# Mach_cau_H_-_Phuc.net
KiCad netlist of a schematic drawn in Altium Designer
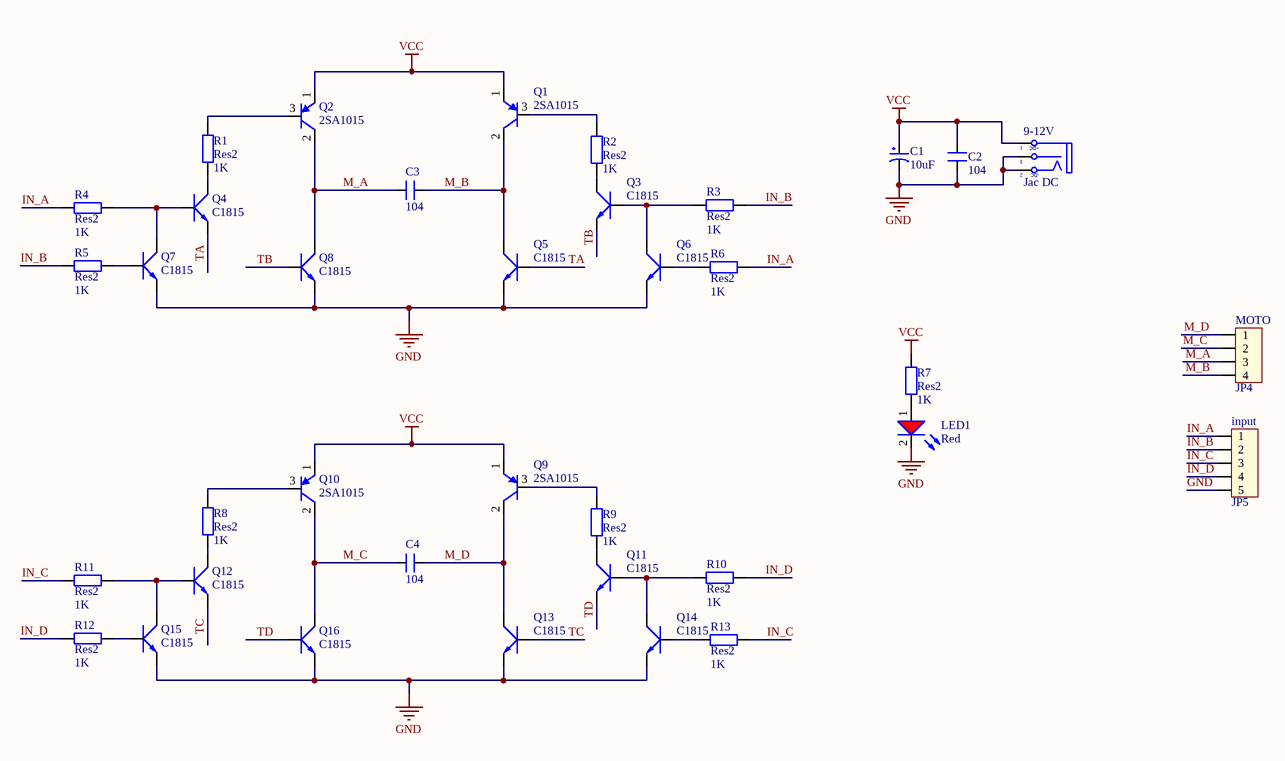
[diagram p0: Mach cau H - Phuc.SchDoc]

(export (version "E")
  (design (tool "Eeschema 10.0.6"))
  (components
    (comp (ref "9-12V")
      (value "Jac DC")
      (footprint "DC-IN")
      (description "Jac DC input")
      (libsource (lib "lpson") (part "DCIN"))
    )
    (comp (ref "C1")
      (value "10uF")
      (footprint "CP1/2")
      (description "Cap P  0,1uF < 22uF , 16 - 50V")
      (libsource (lib "lpson") (part "CP1"))
    )
    (comp (ref "C2")
      (value "104")
      (footprint "CN2")
      (description "Cap np 104 => 105pF")
      (libsource (lib "lpson") (part "CN2"))
    )
    (comp (ref "C3")
      (value "104")
      (footprint "CN2")
      (description "Cap np 104 => 105pF")
      (libsource (lib "lpson") (part "CN2"))
    )
    (comp (ref "C4")
      (value "104")
      (footprint "CN2")
      (description "Cap np 104 => 105pF")
      (libsource (lib "lpson") (part "CN2"))
    )
    (comp (ref "input")
      (value "JP5")
      (footprint "JP5")
      (description "Connector 5")
      (libsource (lib "lpson") (part "Con5"))
    )
    (comp (ref "LED1")
      (value "Red")
      (footprint "LED3R")
      (description "LED Red 2mA 2.0V 3mm")
      (fields (field (name "Comment") "LT0668"))
      (libsource (lib "lpson") (part "LT0668"))
    )
    (comp (ref "MOTO")
      (value "JP4")
      (footprint "DOMINO-MKDS-4-PIN")
      (description "Connector 4")
      (libsource (lib "lpson") (part "Con4"))
    )
    (comp (ref "Q1")
      (value "2SA1015")
      (footprint "QTO-220")
      (description "Trans PNP -50V -150mA TO-92")
      (libsource (lib "lpson") (part "2SA1015"))
    )
    (comp (ref "Q2")
      (value "2SA1015")
      (footprint "QTO-220")
      (description "Trans PNP -50V -150mA TO-92")
      (libsource (lib "lpson") (part "2SA1015"))
    )
    (comp (ref "Q3")
      (value "C1815")
      (footprint "QTO-92")
      (description "NPN 600mW, ECB")
      (libsource (lib "lpson") (part "C1815"))
    )
    (comp (ref "Q4")
      (value "C1815")
      (footprint "QTO-92")
      (description "NPN 600mW, ECB")
      (libsource (lib "lpson") (part "C1815"))
    )
    (comp (ref "Q5")
      (value "C1815")
      (footprint "QTO-220")
      (description "NPN 600mW, ECB")
      (libsource (lib "lpson") (part "C1815"))
    )
    (comp (ref "Q6")
      (value "C1815")
      (footprint "QTO-92")
      (description "NPN 600mW, ECB")
      (libsource (lib "lpson") (part "C1815"))
    )
    (comp (ref "Q7")
      (value "C1815")
      (footprint "QTO-92")
      (description "NPN 600mW, ECB")
      (libsource (lib "lpson") (part "C1815"))
    )
    (comp (ref "Q8")
      (value "C1815")
      (footprint "QTO-220")
      (description "NPN 600mW, ECB")
      (libsource (lib "lpson") (part "C1815"))
    )
    (comp (ref "Q9")
      (value "2SA1015")
      (footprint "QTO-220")
      (description "Trans PNP -50V -150mA TO-92")
      (libsource (lib "lpson") (part "2SA1015"))
    )
    (comp (ref "Q10")
      (value "2SA1015")
      (footprint "QTO-220")
      (description "Trans PNP -50V -150mA TO-92")
      (libsource (lib "lpson") (part "2SA1015"))
    )
    (comp (ref "Q11")
      (value "C1815")
      (footprint "QTO-92")
      (description "NPN 600mW, ECB")
      (libsource (lib "lpson") (part "C1815"))
    )
    (comp (ref "Q12")
      (value "C1815")
      (footprint "QTO-92")
      (description "NPN 600mW, ECB")
      (libsource (lib "lpson") (part "C1815"))
    )
    (comp (ref "Q13")
      (value "C1815")
      (footprint "QTO-220")
      (description "NPN 600mW, ECB")
      (libsource (lib "lpson") (part "C1815"))
    )
    (comp (ref "Q14")
      (value "C1815")
      (footprint "QTO-92")
      (description "NPN 600mW, ECB")
      (libsource (lib "lpson") (part "C1815"))
    )
    (comp (ref "Q15")
      (value "C1815")
      (footprint "QTO-92")
      (description "NPN 600mW, ECB")
      (libsource (lib "lpson") (part "C1815"))
    )
    (comp (ref "Q16")
      (value "C1815")
      (footprint "QTO-220")
      (description "NPN 600mW, ECB")
      (libsource (lib "lpson") (part "C1815"))
    )
    (comp (ref "R1")
      (value "Res2")
      (footprint "RES 1/4W CFR25")
      (description "Resistor")
      (fields (field (name "ALTIUM_VALUE") "1K") (field (name "PUBLISHER") "Altium Limited"))
      (libsource (lib "lpson") (part "Res2"))
    )
    (comp (ref "R2")
      (value "Res2")
      (footprint "RES 1/4W CFR25")
      (description "Resistor")
      (fields (field (name "ALTIUM_VALUE") "1K") (field (name "PUBLISHER") "Altium Limited"))
      (libsource (lib "lpson") (part "Res2"))
    )
    (comp (ref "R3")
      (value "Res2")
      (footprint "RES 1/4W CFR25")
      (description "Resistor")
      (fields (field (name "ALTIUM_VALUE") "1K") (field (name "PUBLISHER") "Altium Limited"))
      (libsource (lib "") (part "Res2_1"))
    )
    (comp (ref "R4")
      (value "Res2")
      (footprint "RES 1/4W CFR25")
      (description "Resistor")
      (fields (field (name "ALTIUM_VALUE") "1K") (field (name "PUBLISHER") "Altium Limited"))
      (libsource (lib "") (part "Res2_2"))
    )
    (comp (ref "R5")
      (value "Res2")
      (footprint "RES 1/4W CFR25")
      (description "Resistor")
      (fields (field (name "ALTIUM_VALUE") "1K") (field (name "PUBLISHER") "Altium Limited"))
      (libsource (lib "") (part "Res2_1"))
    )
    (comp (ref "R6")
      (value "Res2")
      (footprint "RES 1/4W CFR25")
      (description "Resistor")
      (fields (field (name "ALTIUM_VALUE") "1K") (field (name "PUBLISHER") "Altium Limited"))
      (libsource (lib "") (part "Res2_1"))
    )
    (comp (ref "R7")
      (value "Res2")
      (footprint "RES 1/4W CFR25")
      (description "Resistor")
      (fields (field (name "ALTIUM_VALUE") "1K") (field (name "PUBLISHER") "Altium Limited"))
      (libsource (lib "lpson") (part "Res2"))
    )
    (comp (ref "R8")
      (value "Res2")
      (footprint "RES 1/4W CFR25")
      (description "Resistor")
      (fields (field (name "ALTIUM_VALUE") "1K") (field (name "PUBLISHER") "Altium Limited"))
      (libsource (lib "lpson") (part "Res2"))
    )
    (comp (ref "R9")
      (value "Res2")
      (footprint "RES 1/4W CFR25")
      (description "Resistor")
      (fields (field (name "ALTIUM_VALUE") "1K") (field (name "PUBLISHER") "Altium Limited"))
      (libsource (lib "lpson") (part "Res2"))
    )
    (comp (ref "R10")
      (value "Res2")
      (footprint "RES 1/4W CFR25")
      (description "Resistor")
      (fields (field (name "ALTIUM_VALUE") "1K") (field (name "PUBLISHER") "Altium Limited"))
      (libsource (lib "") (part "Res2_1"))
    )
    (comp (ref "R11")
      (value "Res2")
      (footprint "RES 1/4W CFR25")
      (description "Resistor")
      (fields (field (name "ALTIUM_VALUE") "1K") (field (name "PUBLISHER") "Altium Limited"))
      (libsource (lib "") (part "Res2_2"))
    )
    (comp (ref "R12")
      (value "Res2")
      (footprint "RES 1/4W CFR25")
      (description "Resistor")
      (fields (field (name "ALTIUM_VALUE") "1K") (field (name "PUBLISHER") "Altium Limited"))
      (libsource (lib "") (part "Res2_1"))
    )
    (comp (ref "R13")
      (value "Res2")
      (footprint "RES 1/4W CFR25")
      (description "Resistor")
      (fields (field (name "ALTIUM_VALUE") "1K") (field (name "PUBLISHER") "Altium Limited"))
      (libsource (lib "") (part "Res2_1"))
    )
  )
  (nets
    (net (code "1") (name "/IN_A") (class "Default")
      (node (ref "R4") (pin "2") (pinfunction "2_2") (pintype "passive"))
      (node (ref "R6") (pin "2") (pinfunction "2_2") (pintype "passive"))
      (node (ref "input") (pin "1") (pinfunction "1_1") (pintype "passive"))
    )
    (net (code "2") (name "/IN_B") (class "Default")
      (node (ref "R3") (pin "2") (pinfunction "2_2") (pintype "passive"))
      (node (ref "R5") (pin "1") (pinfunction "1_1") (pintype "passive"))
      (node (ref "input") (pin "2") (pinfunction "2_2") (pintype "passive"))
    )
    (net (code "3") (name "/IN_C") (class "Default")
      (node (ref "R11") (pin "2") (pinfunction "2_2") (pintype "passive"))
      (node (ref "R13") (pin "2") (pinfunction "2_2") (pintype "passive"))
      (node (ref "input") (pin "3") (pinfunction "3_3") (pintype "passive"))
    )
    (net (code "4") (name "/IN_D") (class "Default")
      (node (ref "R10") (pin "2") (pinfunction "2_2") (pintype "passive"))
      (node (ref "R12") (pin "1") (pinfunction "1_1") (pintype "passive"))
      (node (ref "input") (pin "4") (pinfunction "4_4") (pintype "passive"))
    )
    (net (code "5") (name "/M_A") (class "Default")
      (node (ref "C3") (pin "1") (pinfunction "1_1") (pintype "passive"))
      (node (ref "MOTO") (pin "3") (pinfunction "3_3") (pintype "passive"))
      (node (ref "Q2") (pin "2") (pinfunction "C_2") (pintype "passive"))
      (node (ref "Q8") (pin "2") (pinfunction "C_2") (pintype "passive"))
    )
    (net (code "6") (name "/M_B") (class "Default")
      (node (ref "C3") (pin "2") (pinfunction "2_2") (pintype "passive"))
      (node (ref "MOTO") (pin "4") (pinfunction "4_4") (pintype "passive"))
      (node (ref "Q1") (pin "2") (pinfunction "C_2") (pintype "passive"))
      (node (ref "Q5") (pin "2") (pinfunction "C_2") (pintype "passive"))
    )
    (net (code "7") (name "/M_C") (class "Default")
      (node (ref "C4") (pin "1") (pinfunction "1_1") (pintype "passive"))
      (node (ref "MOTO") (pin "2") (pinfunction "2_2") (pintype "passive"))
      (node (ref "Q10") (pin "2") (pinfunction "C_2") (pintype "passive"))
      (node (ref "Q16") (pin "2") (pinfunction "C_2") (pintype "passive"))
    )
    (net (code "8") (name "/M_D") (class "Default")
      (node (ref "C4") (pin "2") (pinfunction "2_2") (pintype "passive"))
      (node (ref "MOTO") (pin "1") (pinfunction "1_1") (pintype "passive"))
      (node (ref "Q13") (pin "2") (pinfunction "C_2") (pintype "passive"))
      (node (ref "Q9") (pin "2") (pinfunction "C_2") (pintype "passive"))
    )
    (net (code "9") (name "/TA") (class "Default")
      (node (ref "Q4") (pin "1") (pinfunction "E_1") (pintype "passive"))
      (node (ref "Q5") (pin "3") (pinfunction "B_3") (pintype "passive"))
    )
    (net (code "10") (name "/TB") (class "Default")
      (node (ref "Q3") (pin "1") (pinfunction "E_1") (pintype "passive"))
      (node (ref "Q8") (pin "3") (pinfunction "B_3") (pintype "passive"))
    )
    (net (code "11") (name "/TC") (class "Default")
      (node (ref "Q12") (pin "1") (pinfunction "E_1") (pintype "passive"))
      (node (ref "Q13") (pin "3") (pinfunction "B_3") (pintype "passive"))
    )
    (net (code "12") (name "/TD") (class "Default")
      (node (ref "Q11") (pin "1") (pinfunction "E_1") (pintype "passive"))
      (node (ref "Q16") (pin "3") (pinfunction "B_3") (pintype "passive"))
    )
    (net (code "13") (name "GND") (class "Default")
      (node (ref "9-12V") (pin "2") (pinfunction "TN_2") (pintype "passive"))
      (node (ref "9-12V") (pin "3") (pinfunction "S_3") (pintype "power_in"))
      (node (ref "C1") (pin "2") (pinfunction "2_2") (pintype "passive"))
      (node (ref "C2") (pin "1") (pinfunction "1_1") (pintype "passive"))
      (node (ref "LED1") (pin "2") (pinfunction "K_2") (pintype "passive"))
      (node (ref "Q13") (pin "1") (pinfunction "E_1") (pintype "passive"))
      (node (ref "Q14") (pin "1") (pinfunction "E_1") (pintype "passive"))
      (node (ref "Q15") (pin "1") (pinfunction "E_1") (pintype "passive"))
      (node (ref "Q16") (pin "1") (pinfunction "E_1") (pintype "passive"))
      (node (ref "Q5") (pin "1") (pinfunction "E_1") (pintype "passive"))
      (node (ref "Q6") (pin "1") (pinfunction "E_1") (pintype "passive"))
      (node (ref "Q7") (pin "1") (pinfunction "E_1") (pintype "passive"))
      (node (ref "Q8") (pin "1") (pinfunction "E_1") (pintype "passive"))
      (node (ref "input") (pin "5") (pinfunction "5_5") (pintype "passive"))
    )
    (net (code "14") (name "Net-(LED1-A)") (class "Default")
      (node (ref "LED1") (pin "1") (pinfunction "A_1") (pintype "passive"))
      (node (ref "R7") (pin "1") (pinfunction "1_1") (pintype "passive"))
    )
    (net (code "15") (name "Net-(Q1-B)") (class "Default")
      (node (ref "Q1") (pin "3") (pinfunction "B_3") (pintype "passive"))
      (node (ref "R2") (pin "2") (pinfunction "2_2") (pintype "passive"))
    )
    (net (code "16") (name "Net-(Q2-B)") (class "Default")
      (node (ref "Q2") (pin "3") (pinfunction "B_3") (pintype "passive"))
      (node (ref "R1") (pin "2") (pinfunction "2_2") (pintype "passive"))
    )
    (net (code "17") (name "Net-(Q3-B)") (class "Default")
      (node (ref "Q3") (pin "3") (pinfunction "B_3") (pintype "passive"))
      (node (ref "Q6") (pin "2") (pinfunction "C_2") (pintype "passive"))
      (node (ref "R3") (pin "1") (pinfunction "1_1") (pintype "passive"))
    )
    (net (code "18") (name "Net-(Q3-C)") (class "Default")
      (node (ref "Q3") (pin "2") (pinfunction "C_2") (pintype "passive"))
      (node (ref "R2") (pin "1") (pinfunction "1_1") (pintype "passive"))
    )
    (net (code "19") (name "Net-(Q4-B)") (class "Default")
      (node (ref "Q4") (pin "3") (pinfunction "B_3") (pintype "passive"))
      (node (ref "Q7") (pin "2") (pinfunction "C_2") (pintype "passive"))
      (node (ref "R4") (pin "1") (pinfunction "1_1") (pintype "passive"))
    )
    (net (code "20") (name "Net-(Q4-C)") (class "Default")
      (node (ref "Q4") (pin "2") (pinfunction "C_2") (pintype "passive"))
      (node (ref "R1") (pin "1") (pinfunction "1_1") (pintype "passive"))
    )
    (net (code "21") (name "Net-(Q6-B)") (class "Default")
      (node (ref "Q6") (pin "3") (pinfunction "B_3") (pintype "passive"))
      (node (ref "R6") (pin "1") (pinfunction "1_1") (pintype "passive"))
    )
    (net (code "22") (name "Net-(Q7-B)") (class "Default")
      (node (ref "Q7") (pin "3") (pinfunction "B_3") (pintype "passive"))
      (node (ref "R5") (pin "2") (pinfunction "2_2") (pintype "passive"))
    )
    (net (code "23") (name "Net-(Q9-B)") (class "Default")
      (node (ref "Q9") (pin "3") (pinfunction "B_3") (pintype "passive"))
      (node (ref "R9") (pin "2") (pinfunction "2_2") (pintype "passive"))
    )
    (net (code "24") (name "Net-(Q10-B)") (class "Default")
      (node (ref "Q10") (pin "3") (pinfunction "B_3") (pintype "passive"))
      (node (ref "R8") (pin "2") (pinfunction "2_2") (pintype "passive"))
    )
    (net (code "25") (name "Net-(Q11-B)") (class "Default")
      (node (ref "Q11") (pin "3") (pinfunction "B_3") (pintype "passive"))
      (node (ref "Q14") (pin "2") (pinfunction "C_2") (pintype "passive"))
      (node (ref "R10") (pin "1") (pinfunction "1_1") (pintype "passive"))
    )
    (net (code "26") (name "Net-(Q11-C)") (class "Default")
      (node (ref "Q11") (pin "2") (pinfunction "C_2") (pintype "passive"))
      (node (ref "R9") (pin "1") (pinfunction "1_1") (pintype "passive"))
    )
    (net (code "27") (name "Net-(Q12-B)") (class "Default")
      (node (ref "Q12") (pin "3") (pinfunction "B_3") (pintype "passive"))
      (node (ref "Q15") (pin "2") (pinfunction "C_2") (pintype "passive"))
      (node (ref "R11") (pin "1") (pinfunction "1_1") (pintype "passive"))
    )
    (net (code "28") (name "Net-(Q12-C)") (class "Default")
      (node (ref "Q12") (pin "2") (pinfunction "C_2") (pintype "passive"))
      (node (ref "R8") (pin "1") (pinfunction "1_1") (pintype "passive"))
    )
    (net (code "29") (name "Net-(Q14-B)") (class "Default")
      (node (ref "Q14") (pin "3") (pinfunction "B_3") (pintype "passive"))
      (node (ref "R13") (pin "1") (pinfunction "1_1") (pintype "passive"))
    )
    (net (code "30") (name "Net-(Q15-B)") (class "Default")
      (node (ref "Q15") (pin "3") (pinfunction "B_3") (pintype "passive"))
      (node (ref "R12") (pin "2") (pinfunction "2_2") (pintype "passive"))
    )
    (net (code "31") (name "VCC") (class "Default")
      (node (ref "9-12V") (pin "1") (pinfunction "T_1") (pintype "passive"))
      (node (ref "C1") (pin "1") (pinfunction "1_1") (pintype "passive"))
      (node (ref "C2") (pin "2") (pinfunction "2_2") (pintype "passive"))
      (node (ref "Q1") (pin "1") (pinfunction "E_1") (pintype "passive"))
      (node (ref "Q10") (pin "1") (pinfunction "E_1") (pintype "passive"))
      (node (ref "Q2") (pin "1") (pinfunction "E_1") (pintype "passive"))
      (node (ref "Q9") (pin "1") (pinfunction "E_1") (pintype "passive"))
      (node (ref "R7") (pin "2") (pinfunction "2_2") (pintype "passive"))
    )
  )
)
